# 04_USB.net
KiCad netlist of a schematic drawn in Altium Designer
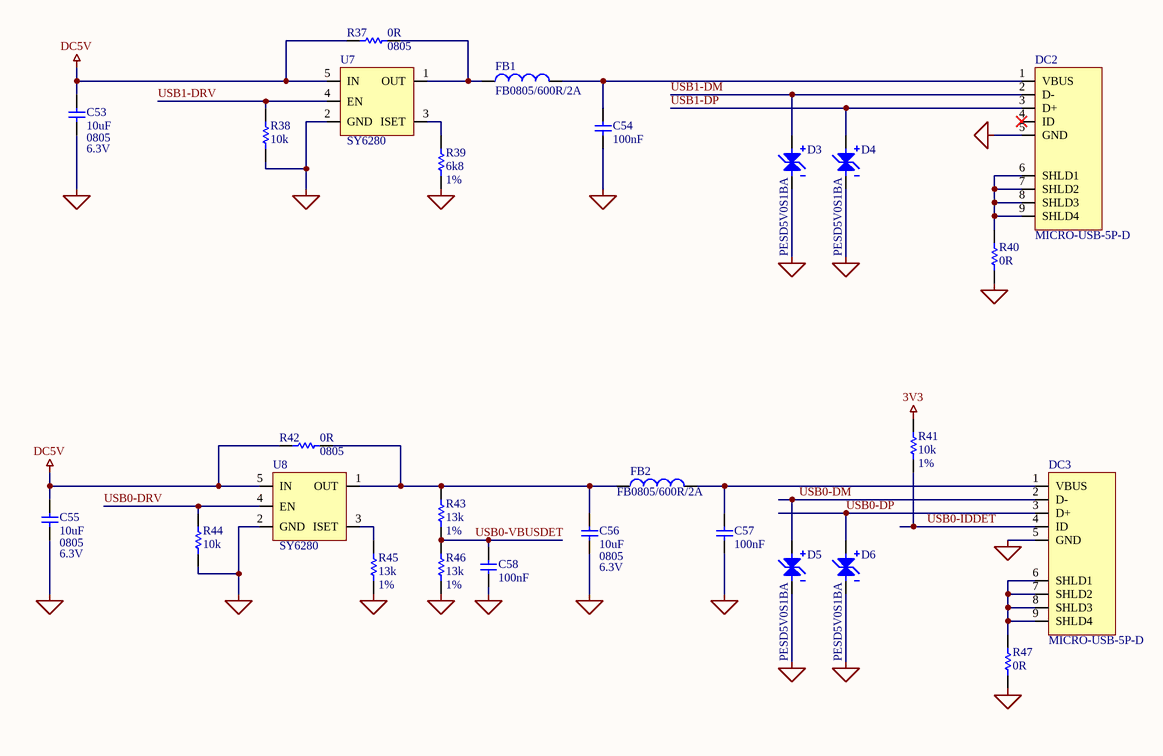
[diagram p0: [04]USB.SchDoc]

(export (version "E")
  (design (tool "Eeschema 10.0.6"))
  (components
    (comp (ref "C53")
      (value "10uF")
      (footprint "C0805")
      (description "SMD Capacitor")
      (fields
        (field (name "MPN") "?")
        (field (name "TOLERANCE") "20%")
        (field (name "VOLTAGE") "6.3V")
        (field (name "PACKAGE / CASE") "0805")
      )
      (libsource (lib "local") (part "CAP"))
    )
    (comp (ref "C54")
      (value "100nF")
      (footprint "C0402")
      (description "SMD Capacitor")
      (fields (field (name "MPN") "?") (field (name "TOLERANCE") "20%"))
      (libsource (lib "local") (part "CAP"))
    )
    (comp (ref "C55")
      (value "10uF")
      (footprint "C0805")
      (description "SMD Capacitor")
      (fields
        (field (name "MPN") "?")
        (field (name "TOLERANCE") "20%")
        (field (name "VOLTAGE") "6.3V")
        (field (name "PACKAGE / CASE") "0805")
      )
      (libsource (lib "local") (part "CAP"))
    )
    (comp (ref "C56")
      (value "10uF")
      (footprint "C0805")
      (description "SMD Capacitor")
      (fields
        (field (name "MPN") "?")
        (field (name "TOLERANCE") "20%")
        (field (name "VOLTAGE") "6.3V")
        (field (name "PACKAGE / CASE") "0805")
      )
      (libsource (lib "local") (part "CAP"))
    )
    (comp (ref "C57")
      (value "100nF")
      (footprint "C0402")
      (description "SMD Capacitor")
      (fields (field (name "MPN") "?") (field (name "TOLERANCE") "20%"))
      (libsource (lib "local") (part "CAP"))
    )
    (comp (ref "C58")
      (value "100nF")
      (footprint "C0402")
      (description "SMD Capacitor")
      (fields (field (name "MPN") "?") (field (name "TOLERANCE") "20%"))
      (libsource (lib "local") (part "CAP"))
    )
    (comp (ref "D3")
      (value "SMD ESD Diode")
      (description "SMD ESD Diode Chip")
      (fields (field (name "MANUFACTURER") "?") (field (name "MPN") "PESD5V0S1BA"))
      (libsource (lib "local") (part "DIODE ESD"))
    )
    (comp (ref "D4")
      (value "SMD ESD Diode")
      (description "SMD ESD Diode Chip")
      (fields (field (name "MANUFACTURER") "?") (field (name "MPN") "PESD5V0S1BA"))
      (libsource (lib "local") (part "DIODE ESD"))
    )
    (comp (ref "D5")
      (value "SMD ESD Diode")
      (description "SMD ESD Diode Chip")
      (fields (field (name "MANUFACTURER") "?") (field (name "MPN") "PESD5V0S1BA"))
      (libsource (lib "local") (part "DIODE ESD"))
    )
    (comp (ref "D6")
      (value "SMD ESD Diode")
      (description "SMD ESD Diode Chip")
      (fields (field (name "MANUFACTURER") "?") (field (name "MPN") "PESD5V0S1BA"))
      (libsource (lib "local") (part "DIODE ESD"))
    )
    (comp (ref "DC2")
      (value "SMD USB Jack")
      (description "SMD USB DC Jack")
      (fields (field (name "MPN") "MICRO-USB-5P-D"))
      (libsource (lib "local") (part "USB-JACK"))
    )
    (comp (ref "DC3")
      (value "SMD USB Jack")
      (description "SMD USB DC Jack")
      (fields (field (name "MPN") "MICRO-USB-5P-D"))
      (libsource (lib "local") (part "USB-JACK"))
    )
    (comp (ref "FB1")
      (value "FB0805/600R/2A")
      (description "SMD Coil")
      (fields (field (name "MPN") "?") (field (name "Comment") "SMD Coil Chip"))
      (libsource (lib "local") (part "COIL"))
    )
    (comp (ref "FB2")
      (value "FB0805/600R/2A")
      (description "SMD Coil")
      (fields (field (name "MPN") "?") (field (name "Comment") "SMD Coil Chip"))
      (libsource (lib "local") (part "COIL"))
    )
    (comp (ref "R37")
      (value "0R")
      (description "SMD Resistor")
      (fields (field (name "PACKAGE / CASE") "0805") (field (name "MPN") "?") (field (name "TOLERANCE") "1%"))
      (libsource (lib "local") (part "RES"))
    )
    (comp (ref "R38")
      (value "10k")
      (description "SMD Resistor")
      (fields (field (name "MPN") "?") (field (name "TOLERANCE") "1%"))
      (libsource (lib "local") (part "RES"))
    )
    (comp (ref "R39")
      (value "6k8")
      (description "SMD Resistor")
      (fields
        (field (name "MPN") "?")
        (field (name "TOLERANCE") "1%")
        (field (name "Comment") "SMD Resistor Chip")
      )
      (libsource (lib "local") (part "RES"))
    )
    (comp (ref "R40")
      (value "0R")
      (description "SMD Resistor")
      (fields (field (name "MPN") "?") (field (name "TOLERANCE") "1%"))
      (libsource (lib "local") (part "RES"))
    )
    (comp (ref "R41")
      (value "10k")
      (description "SMD Resistor")
      (fields
        (field (name "MPN") "?")
        (field (name "TOLERANCE") "1%")
        (field (name "Comment") "SMD Resistor Chip")
      )
      (libsource (lib "local") (part "RES"))
    )
    (comp (ref "R42")
      (value "0R")
      (description "SMD Resistor")
      (fields (field (name "PACKAGE / CASE") "0805") (field (name "MPN") "?") (field (name "TOLERANCE") "1%"))
      (libsource (lib "local") (part "RES"))
    )
    (comp (ref "R43")
      (value "13k")
      (description "SMD Resistor")
      (fields
        (field (name "MPN") "?")
        (field (name "TOLERANCE") "1%")
        (field (name "Comment") "SMD Resistor Chip")
      )
      (libsource (lib "local") (part "RES"))
    )
    (comp (ref "R44")
      (value "10k")
      (description "SMD Resistor")
      (fields (field (name "MPN") "?") (field (name "TOLERANCE") "1%"))
      (libsource (lib "local") (part "RES"))
    )
    (comp (ref "R45")
      (value "13k")
      (description "SMD Resistor")
      (fields
        (field (name "MPN") "?")
        (field (name "TOLERANCE") "1%")
        (field (name "Comment") "SMD Resistor Chip")
      )
      (libsource (lib "local") (part "RES"))
    )
    (comp (ref "R46")
      (value "13k")
      (description "SMD Resistor")
      (fields
        (field (name "MPN") "?")
        (field (name "TOLERANCE") "1%")
        (field (name "Comment") "SMD Resistor Chip")
      )
      (libsource (lib "local") (part "RES"))
    )
    (comp (ref "R47")
      (value "0R")
      (description "SMD Resistor")
      (fields (field (name "MPN") "?") (field (name "TOLERANCE") "1%"))
      (libsource (lib "local") (part "RES"))
    )
    (comp (ref "U7")
      (value "SMD Power Distribution Switch")
      (description "Low Loss Power Distribution Switch")
      (fields (field (name "MPN") "SY6280") (field (name "MANUFACTURER") "SILERGY"))
      (libsource (lib "local") (part "SY6280"))
    )
    (comp (ref "U8")
      (value "SMD Power Distribution Switch")
      (description "Low Loss Power Distribution Switch")
      (fields (field (name "MPN") "SY6280") (field (name "MANUFACTURER") "SILERGY"))
      (libsource (lib "local") (part "SY6280"))
    )
  )
  (nets
    (net (code "1") (name "/USB0-DM") (class "Default")
      (node (ref "D5") (pin "1") (pinfunction "1_1") (pintype "passive"))
      (node (ref "DC3") (pin "2") (pinfunction "D-_2") (pintype "passive"))
    )
    (net (code "2") (name "/USB0-DP") (class "Default")
      (node (ref "D6") (pin "1") (pinfunction "1_1") (pintype "passive"))
      (node (ref "DC3") (pin "3") (pinfunction "D+_3") (pintype "passive"))
    )
    (net (code "3") (name "/USB0-DRV") (class "Default")
      (node (ref "R44") (pin "1") (pinfunction "1_1") (pintype "passive"))
      (node (ref "U8") (pin "4") (pinfunction "EN_4") (pintype "passive"))
    )
    (net (code "4") (name "/USB0-IDDET") (class "Default")
      (node (ref "DC3") (pin "4") (pinfunction "ID_4") (pintype "passive"))
      (node (ref "R41") (pin "2") (pinfunction "2_2") (pintype "passive"))
    )
    (net (code "5") (name "/USB0-VBUSDET") (class "Default")
      (node (ref "C58") (pin "2") (pinfunction "2_2") (pintype "passive"))
      (node (ref "R43") (pin "2") (pinfunction "2_2") (pintype "passive"))
      (node (ref "R46") (pin "1") (pinfunction "1_1") (pintype "passive"))
    )
    (net (code "6") (name "/USB1-DM") (class "Default")
      (node (ref "D3") (pin "1") (pinfunction "1_1") (pintype "passive"))
      (node (ref "DC2") (pin "2") (pinfunction "D-_2") (pintype "passive"))
    )
    (net (code "7") (name "/USB1-DP") (class "Default")
      (node (ref "D4") (pin "1") (pinfunction "1_1") (pintype "passive"))
      (node (ref "DC2") (pin "3") (pinfunction "D+_3") (pintype "passive"))
    )
    (net (code "8") (name "/USB1-DRV") (class "Default")
      (node (ref "R38") (pin "1") (pinfunction "1_1") (pintype "passive"))
      (node (ref "U7") (pin "4") (pinfunction "EN_4") (pintype "passive"))
    )
    (net (code "9") (name "3V3") (class "Default")
      (node (ref "R41") (pin "1") (pinfunction "1_1") (pintype "passive"))
    )
    (net (code "10") (name "DC5V") (class "Default")
      (node (ref "C53") (pin "1") (pinfunction "1_1") (pintype "passive"))
      (node (ref "C55") (pin "1") (pinfunction "1_1") (pintype "passive"))
      (node (ref "R37") (pin "1") (pinfunction "1_1") (pintype "passive"))
      (node (ref "R42") (pin "1") (pinfunction "1_1") (pintype "passive"))
      (node (ref "U7") (pin "5") (pinfunction "IN_5") (pintype "passive"))
      (node (ref "U8") (pin "5") (pinfunction "IN_5") (pintype "passive"))
    )
    (net (code "11") (name "Net-(DC2-SHLD1)") (class "Default")
      (node (ref "DC2") (pin "6") (pinfunction "SHLD1_6") (pintype "passive"))
      (node (ref "DC2") (pin "7") (pinfunction "SHLD2_7") (pintype "passive"))
      (node (ref "DC2") (pin "8") (pinfunction "SHLD3_8") (pintype "passive"))
      (node (ref "DC2") (pin "9") (pinfunction "SHLD4_9") (pintype "passive"))
      (node (ref "R40") (pin "1") (pinfunction "1_1") (pintype "passive"))
    )
    (net (code "12") (name "Net-(DC2-VBUS)") (class "Default")
      (node (ref "C54") (pin "2") (pinfunction "2_2") (pintype "passive"))
      (node (ref "DC2") (pin "1") (pinfunction "VBUS_1") (pintype "passive"))
      (node (ref "FB1") (pin "2") (pinfunction "2_2") (pintype "passive"))
    )
    (net (code "13") (name "Net-(DC3-SHLD1)") (class "Default")
      (node (ref "DC3") (pin "6") (pinfunction "SHLD1_6") (pintype "passive"))
      (node (ref "DC3") (pin "7") (pinfunction "SHLD2_7") (pintype "passive"))
      (node (ref "DC3") (pin "8") (pinfunction "SHLD3_8") (pintype "passive"))
      (node (ref "DC3") (pin "9") (pinfunction "SHLD4_9") (pintype "passive"))
      (node (ref "R47") (pin "1") (pinfunction "1_1") (pintype "passive"))
    )
    (net (code "14") (name "Net-(DC3-VBUS)") (class "Default")
      (node (ref "C57") (pin "2") (pinfunction "2_2") (pintype "passive"))
      (node (ref "DC3") (pin "1") (pinfunction "VBUS_1") (pintype "passive"))
      (node (ref "FB2") (pin "2") (pinfunction "2_2") (pintype "passive"))
    )
    (net (code "15") (name "Net-(U7-ISET)") (class "Default")
      (node (ref "R39") (pin "1") (pinfunction "1_1") (pintype "passive"))
      (node (ref "U7") (pin "3") (pinfunction "ISET_3") (pintype "passive"))
    )
    (net (code "16") (name "Net-(U7-OUT)") (class "Default")
      (node (ref "FB1") (pin "1") (pinfunction "1_1") (pintype "passive"))
      (node (ref "R37") (pin "2") (pinfunction "2_2") (pintype "passive"))
      (node (ref "U7") (pin "1") (pinfunction "OUT_1") (pintype "passive"))
    )
    (net (code "17") (name "Net-(U8-ISET)") (class "Default")
      (node (ref "R45") (pin "1") (pinfunction "1_1") (pintype "passive"))
      (node (ref "U8") (pin "3") (pinfunction "ISET_3") (pintype "passive"))
    )
    (net (code "18") (name "Net-(U8-OUT)") (class "Default")
      (node (ref "C56") (pin "1") (pinfunction "1_1") (pintype "passive"))
      (node (ref "FB2") (pin "1") (pinfunction "1_1") (pintype "passive"))
      (node (ref "R42") (pin "2") (pinfunction "2_2") (pintype "passive"))
      (node (ref "R43") (pin "1") (pinfunction "1_1") (pintype "passive"))
      (node (ref "U8") (pin "1") (pinfunction "OUT_1") (pintype "passive"))
    )
    (net (code "19") (name "SGND") (class "Default")
      (node (ref "C53") (pin "2") (pinfunction "2_2") (pintype "passive"))
      (node (ref "C54") (pin "1") (pinfunction "1_1") (pintype "passive"))
      (node (ref "C55") (pin "2") (pinfunction "2_2") (pintype "passive"))
      (node (ref "C56") (pin "2") (pinfunction "2_2") (pintype "passive"))
      (node (ref "C57") (pin "1") (pinfunction "1_1") (pintype "passive"))
      (node (ref "C58") (pin "1") (pinfunction "1_1") (pintype "passive"))
      (node (ref "D3") (pin "2") (pinfunction "2_2") (pintype "passive"))
      (node (ref "D4") (pin "2") (pinfunction "2_2") (pintype "passive"))
      (node (ref "D5") (pin "2") (pinfunction "2_2") (pintype "passive"))
      (node (ref "D6") (pin "2") (pinfunction "2_2") (pintype "passive"))
      (node (ref "DC2") (pin "5") (pinfunction "GND_5") (pintype "passive"))
      (node (ref "DC3") (pin "5") (pinfunction "GND_5") (pintype "passive"))
      (node (ref "R38") (pin "2") (pinfunction "2_2") (pintype "passive"))
      (node (ref "R39") (pin "2") (pinfunction "2_2") (pintype "passive"))
      (node (ref "R40") (pin "2") (pinfunction "2_2") (pintype "passive"))
      (node (ref "R44") (pin "2") (pinfunction "2_2") (pintype "passive"))
      (node (ref "R45") (pin "2") (pinfunction "2_2") (pintype "passive"))
      (node (ref "R46") (pin "2") (pinfunction "2_2") (pintype "passive"))
      (node (ref "R47") (pin "2") (pinfunction "2_2") (pintype "passive"))
      (node (ref "U7") (pin "2") (pinfunction "GND_2") (pintype "passive"))
      (node (ref "U8") (pin "2") (pinfunction "GND_2") (pintype "passive"))
    )
    (net (code "20") (name "unconnected-(DC2-ID-Pad4)") (class "Default")
      (node (ref "DC2") (pin "4") (pinfunction "ID_4") (pintype "passive+no_connect"))
    )
  )
)
